# box.net
KiCad netlist of a schematic drawn in EAGLE
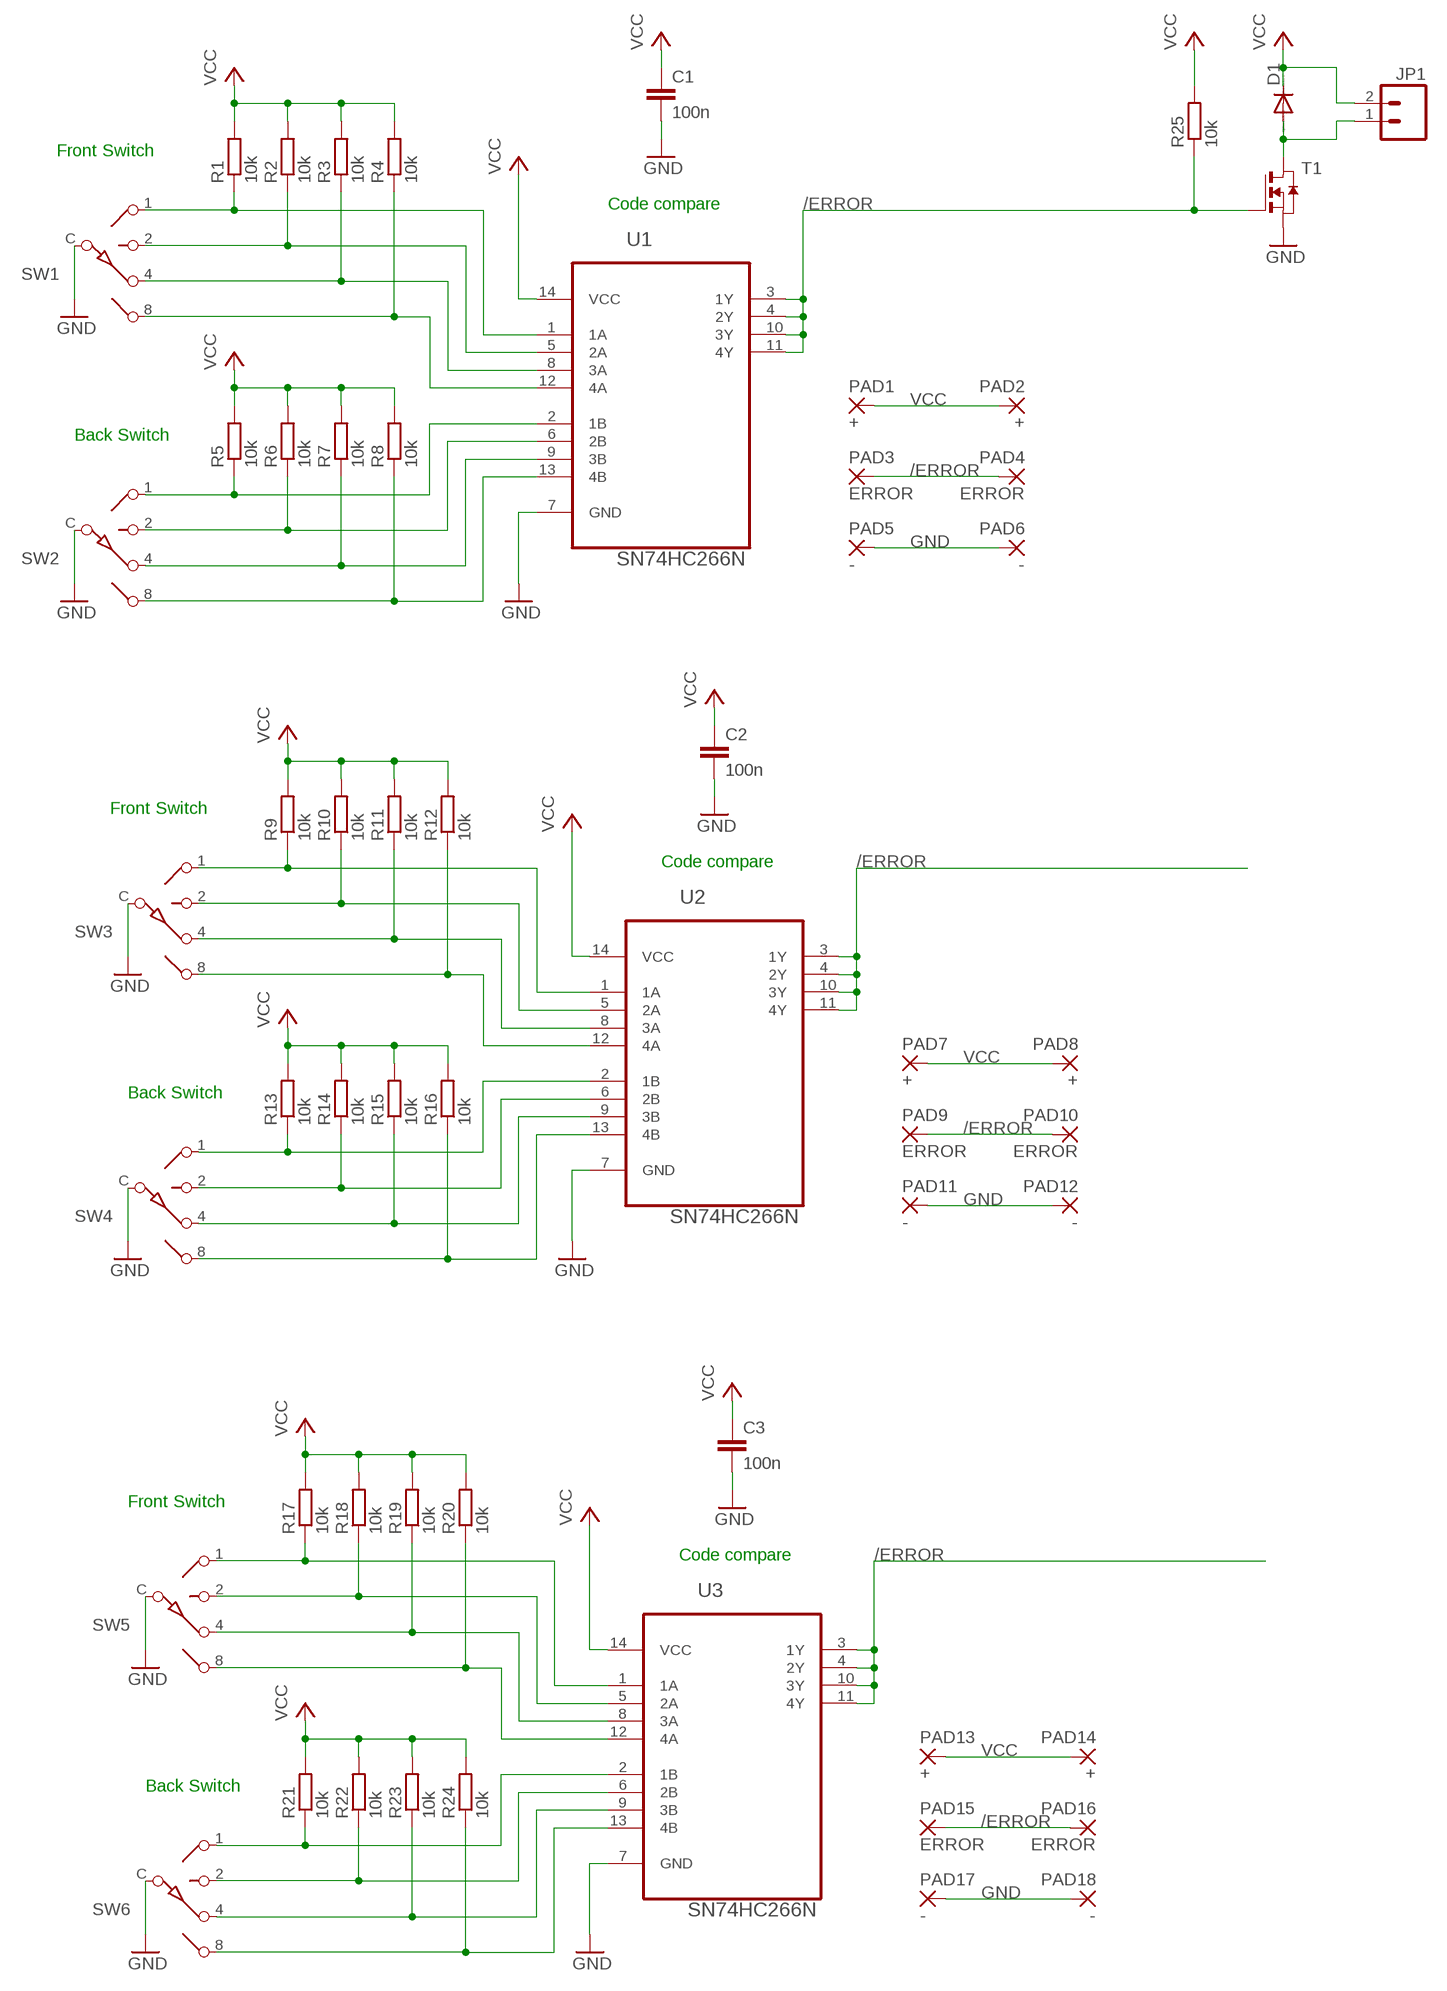
[diagram p0: schematic, sheet 1]

(export (version "E")
  (design (tool "Eeschema 10.0.6"))
  (components
    (comp (ref "C1")
      (value "100n")
      (footprint "eagle-import:C0805")
      (libsource (lib "eagle-import") (part "C-EUC0805"))
    )
    (comp (ref "C2")
      (value "100n")
      (footprint "eagle-import:C0805")
      (libsource (lib "eagle-import") (part "C-EUC0805"))
    )
    (comp (ref "C3")
      (value "100n")
      (footprint "eagle-import:C0805")
      (libsource (lib "eagle-import") (part "C-EUC0805"))
    )
    (comp (ref "D1")
      (value "DIODE-DO41-7.6")
      (footprint "eagle-import:DO41-7.6")
      (libsource (lib "eagle-import") (part "DIODE-DO41-7.6"))
    )
    (comp (ref "JP1")
      (value "M02JST-PTH-2")
      (footprint "eagle-import:JST-2-PTH")
      (libsource (lib "eagle-import") (part "M02JST-PTH-2"))
    )
    (comp (ref "PAD1")
      (value "+")
      (footprint "eagle-import:2,15_1,0")
      (libsource (lib "eagle-import") (part "2,15/1,0"))
    )
    (comp (ref "PAD2")
      (value "+")
      (footprint "eagle-import:2,15_1,0")
      (libsource (lib "eagle-import") (part "2,15/1,0"))
    )
    (comp (ref "PAD3")
      (value "ERROR")
      (footprint "eagle-import:2,15_1,0")
      (libsource (lib "eagle-import") (part "2,15/1,0"))
    )
    (comp (ref "PAD4")
      (value "ERROR")
      (footprint "eagle-import:2,15_1,0")
      (libsource (lib "eagle-import") (part "2,15/1,0"))
    )
    (comp (ref "PAD5")
      (value "-")
      (footprint "eagle-import:2,15_1,0")
      (libsource (lib "eagle-import") (part "2,15/1,0"))
    )
    (comp (ref "PAD6")
      (value "-")
      (footprint "eagle-import:2,15_1,0")
      (libsource (lib "eagle-import") (part "2,15/1,0"))
    )
    (comp (ref "PAD7")
      (value "+")
      (footprint "eagle-import:2,15_1,0")
      (libsource (lib "eagle-import") (part "2,15/1,0"))
    )
    (comp (ref "PAD8")
      (value "+")
      (footprint "eagle-import:2,15_1,0")
      (libsource (lib "eagle-import") (part "2,15/1,0"))
    )
    (comp (ref "PAD9")
      (value "ERROR")
      (footprint "eagle-import:2,15_1,0")
      (libsource (lib "eagle-import") (part "2,15/1,0"))
    )
    (comp (ref "PAD10")
      (value "ERROR")
      (footprint "eagle-import:2,15_1,0")
      (libsource (lib "eagle-import") (part "2,15/1,0"))
    )
    (comp (ref "PAD11")
      (value "-")
      (footprint "eagle-import:2,15_1,0")
      (libsource (lib "eagle-import") (part "2,15/1,0"))
    )
    (comp (ref "PAD12")
      (value "-")
      (footprint "eagle-import:2,15_1,0")
      (libsource (lib "eagle-import") (part "2,15/1,0"))
    )
    (comp (ref "PAD13")
      (value "+")
      (footprint "eagle-import:2,15_1,0")
      (libsource (lib "eagle-import") (part "2,15/1,0"))
    )
    (comp (ref "PAD14")
      (value "+")
      (footprint "eagle-import:2,15_1,0")
      (libsource (lib "eagle-import") (part "2,15/1,0"))
    )
    (comp (ref "PAD15")
      (value "ERROR")
      (footprint "eagle-import:2,15_1,0")
      (libsource (lib "eagle-import") (part "2,15/1,0"))
    )
    (comp (ref "PAD16")
      (value "ERROR")
      (footprint "eagle-import:2,15_1,0")
      (libsource (lib "eagle-import") (part "2,15/1,0"))
    )
    (comp (ref "PAD17")
      (value "-")
      (footprint "eagle-import:2,15_1,0")
      (libsource (lib "eagle-import") (part "2,15/1,0"))
    )
    (comp (ref "PAD18")
      (value "-")
      (footprint "eagle-import:2,15_1,0")
      (libsource (lib "eagle-import") (part "2,15/1,0"))
    )
    (comp (ref "R1")
      (value "10k")
      (footprint "eagle-import:R0805")
      (libsource (lib "eagle-import") (part "R-EU_R0805"))
    )
    (comp (ref "R2")
      (value "10k")
      (footprint "eagle-import:R0805")
      (libsource (lib "eagle-import") (part "R-EU_R0805"))
    )
    (comp (ref "R3")
      (value "10k")
      (footprint "eagle-import:R0805")
      (libsource (lib "eagle-import") (part "R-EU_R0805"))
    )
    (comp (ref "R4")
      (value "10k")
      (footprint "eagle-import:R0805")
      (libsource (lib "eagle-import") (part "R-EU_R0805"))
    )
    (comp (ref "R5")
      (value "10k")
      (footprint "eagle-import:R0805")
      (libsource (lib "eagle-import") (part "R-EU_R0805"))
    )
    (comp (ref "R6")
      (value "10k")
      (footprint "eagle-import:R0805")
      (libsource (lib "eagle-import") (part "R-EU_R0805"))
    )
    (comp (ref "R7")
      (value "10k")
      (footprint "eagle-import:R0805")
      (libsource (lib "eagle-import") (part "R-EU_R0805"))
    )
    (comp (ref "R8")
      (value "10k")
      (footprint "eagle-import:R0805")
      (libsource (lib "eagle-import") (part "R-EU_R0805"))
    )
    (comp (ref "R9")
      (value "10k")
      (footprint "eagle-import:R0805")
      (libsource (lib "eagle-import") (part "R-EU_R0805"))
    )
    (comp (ref "R10")
      (value "10k")
      (footprint "eagle-import:R0805")
      (libsource (lib "eagle-import") (part "R-EU_R0805"))
    )
    (comp (ref "R11")
      (value "10k")
      (footprint "eagle-import:R0805")
      (libsource (lib "eagle-import") (part "R-EU_R0805"))
    )
    (comp (ref "R12")
      (value "10k")
      (footprint "eagle-import:R0805")
      (libsource (lib "eagle-import") (part "R-EU_R0805"))
    )
    (comp (ref "R13")
      (value "10k")
      (footprint "eagle-import:R0805")
      (libsource (lib "eagle-import") (part "R-EU_R0805"))
    )
    (comp (ref "R14")
      (value "10k")
      (footprint "eagle-import:R0805")
      (libsource (lib "eagle-import") (part "R-EU_R0805"))
    )
    (comp (ref "R15")
      (value "10k")
      (footprint "eagle-import:R0805")
      (libsource (lib "eagle-import") (part "R-EU_R0805"))
    )
    (comp (ref "R16")
      (value "10k")
      (footprint "eagle-import:R0805")
      (libsource (lib "eagle-import") (part "R-EU_R0805"))
    )
    (comp (ref "R17")
      (value "10k")
      (footprint "eagle-import:R0805")
      (libsource (lib "eagle-import") (part "R-EU_R0805"))
    )
    (comp (ref "R18")
      (value "10k")
      (footprint "eagle-import:R0805")
      (libsource (lib "eagle-import") (part "R-EU_R0805"))
    )
    (comp (ref "R19")
      (value "10k")
      (footprint "eagle-import:R0805")
      (libsource (lib "eagle-import") (part "R-EU_R0805"))
    )
    (comp (ref "R20")
      (value "10k")
      (footprint "eagle-import:R0805")
      (libsource (lib "eagle-import") (part "R-EU_R0805"))
    )
    (comp (ref "R21")
      (value "10k")
      (footprint "eagle-import:R0805")
      (libsource (lib "eagle-import") (part "R-EU_R0805"))
    )
    (comp (ref "R22")
      (value "10k")
      (footprint "eagle-import:R0805")
      (libsource (lib "eagle-import") (part "R-EU_R0805"))
    )
    (comp (ref "R23")
      (value "10k")
      (footprint "eagle-import:R0805")
      (libsource (lib "eagle-import") (part "R-EU_R0805"))
    )
    (comp (ref "R24")
      (value "10k")
      (footprint "eagle-import:R0805")
      (libsource (lib "eagle-import") (part "R-EU_R0805"))
    )
    (comp (ref "R25")
      (value "10k")
      (footprint "eagle-import:R0805")
      (libsource (lib "eagle-import") (part "R-EU_R0805"))
    )
    (comp (ref "SW1")
      (value "ROTARY-SWITCH-10POSMCRM4HAF-10R-V-B")
      (footprint "eagle-import:MCRM4HAF")
      (libsource (lib "eagle-import") (part "ROTARY-SWITCH-10POSMCRM4HAF-10R-V-B"))
    )
    (comp (ref "SW2")
      (value "ROTARY-SWITCH-10POSMCRM4HAF-10R-V-B")
      (footprint "eagle-import:MCRM4HAF")
      (libsource (lib "eagle-import") (part "ROTARY-SWITCH-10POSMCRM4HAF-10R-V-B"))
    )
    (comp (ref "SW3")
      (value "ROTARY-SWITCH-10POSMCRM4HAF-10R-V-B")
      (footprint "eagle-import:MCRM4HAF")
      (libsource (lib "eagle-import") (part "ROTARY-SWITCH-10POSMCRM4HAF-10R-V-B"))
    )
    (comp (ref "SW4")
      (value "ROTARY-SWITCH-10POSMCRM4HAF-10R-V-B")
      (footprint "eagle-import:MCRM4HAF")
      (libsource (lib "eagle-import") (part "ROTARY-SWITCH-10POSMCRM4HAF-10R-V-B"))
    )
    (comp (ref "SW5")
      (value "ROTARY-SWITCH-10POSMCRM4HAF-10R-V-B")
      (footprint "eagle-import:MCRM4HAF")
      (libsource (lib "eagle-import") (part "ROTARY-SWITCH-10POSMCRM4HAF-10R-V-B"))
    )
    (comp (ref "SW6")
      (value "ROTARY-SWITCH-10POSMCRM4HAF-10R-V-B")
      (footprint "eagle-import:MCRM4HAF")
      (libsource (lib "eagle-import") (part "ROTARY-SWITCH-10POSMCRM4HAF-10R-V-B"))
    )
    (comp (ref "T1")
      (value "TSM3442")
      (footprint "eagle-import:SOT23-6")
      (libsource (lib "eagle-import") (part "TSM3442"))
    )
    (comp (ref "U1")
      (value "SN74HC266N")
      (footprint "eagle-import:DIP254P762X508-14")
      (libsource (lib "eagle-import") (part "SN74HC266N"))
    )
    (comp (ref "U2")
      (value "SN74HC266N")
      (footprint "eagle-import:DIP254P762X508-14")
      (libsource (lib "eagle-import") (part "SN74HC266N"))
    )
    (comp (ref "U3")
      (value "SN74HC266N")
      (footprint "eagle-import:DIP254P762X508-14")
      (libsource (lib "eagle-import") (part "SN74HC266N"))
    )
  )
  (nets
    (net (code "1") (name "/{slash}ERROR") (class "Default")
      (node (ref "PAD10") (pin "1") (pinfunction "P_1") (pintype "passive"))
      (node (ref "PAD15") (pin "1") (pinfunction "P_1") (pintype "passive"))
      (node (ref "PAD16") (pin "1") (pinfunction "P_1") (pintype "passive"))
      (node (ref "PAD3") (pin "1") (pinfunction "P_1") (pintype "passive"))
      (node (ref "PAD4") (pin "1") (pinfunction "P_1") (pintype "passive"))
      (node (ref "PAD9") (pin "1") (pinfunction "P_1") (pintype "passive"))
      (node (ref "R25") (pin "1") (pinfunction "1_1") (pintype "passive"))
      (node (ref "T1") (pin "3") (pinfunction "G_3") (pintype "passive"))
      (node (ref "U1") (pin "10") (pinfunction "3Y_10") (pintype "output"))
      (node (ref "U1") (pin "11") (pinfunction "4Y_11") (pintype "output"))
      (node (ref "U1") (pin "3") (pinfunction "1Y_3") (pintype "output"))
      (node (ref "U1") (pin "4") (pinfunction "2Y_4") (pintype "output"))
      (node (ref "U2") (pin "10") (pinfunction "3Y_10") (pintype "output"))
      (node (ref "U2") (pin "11") (pinfunction "4Y_11") (pintype "output"))
      (node (ref "U2") (pin "3") (pinfunction "1Y_3") (pintype "output"))
      (node (ref "U2") (pin "4") (pinfunction "2Y_4") (pintype "output"))
      (node (ref "U3") (pin "10") (pinfunction "3Y_10") (pintype "output"))
      (node (ref "U3") (pin "11") (pinfunction "4Y_11") (pintype "output"))
      (node (ref "U3") (pin "3") (pinfunction "1Y_3") (pintype "output"))
      (node (ref "U3") (pin "4") (pinfunction "2Y_4") (pintype "output"))
    )
    (net (code "2") (name "GND") (class "Default")
      (node (ref "C1") (pin "2") (pinfunction "2_2") (pintype "passive"))
      (node (ref "C2") (pin "2") (pinfunction "2_2") (pintype "passive"))
      (node (ref "C3") (pin "2") (pinfunction "2_2") (pintype "passive"))
      (node (ref "PAD11") (pin "1") (pinfunction "P_1") (pintype "passive"))
      (node (ref "PAD12") (pin "1") (pinfunction "P_1") (pintype "passive"))
      (node (ref "PAD17") (pin "1") (pinfunction "P_1") (pintype "passive"))
      (node (ref "PAD18") (pin "1") (pinfunction "P_1") (pintype "passive"))
      (node (ref "PAD5") (pin "1") (pinfunction "P_1") (pintype "passive"))
      (node (ref "PAD6") (pin "1") (pinfunction "P_1") (pintype "passive"))
      (node (ref "SW1") (pin "C") (pinfunction "C_C") (pintype "passive"))
      (node (ref "SW2") (pin "C") (pinfunction "C_C") (pintype "passive"))
      (node (ref "SW3") (pin "C") (pinfunction "C_C") (pintype "passive"))
      (node (ref "SW4") (pin "C") (pinfunction "C_C") (pintype "passive"))
      (node (ref "SW5") (pin "C") (pinfunction "C_C") (pintype "passive"))
      (node (ref "SW6") (pin "C") (pinfunction "C_C") (pintype "passive"))
      (node (ref "T1") (pin "4") (pinfunction "S_4") (pintype "passive"))
      (node (ref "U1") (pin "7") (pinfunction "GND_7") (pintype "passive"))
      (node (ref "U2") (pin "7") (pinfunction "GND_7") (pintype "passive"))
      (node (ref "U3") (pin "7") (pinfunction "GND_7") (pintype "passive"))
    )
    (net (code "3") (name "Net-(D1-PadA)") (class "Default")
      (node (ref "D1") (pin "A") (pinfunction "A_A") (pintype "passive"))
      (node (ref "JP1") (pin "1") (pinfunction "1_1") (pintype "passive"))
      (node (ref "T1") (pin "1") (pinfunction "D_1") (pintype "passive"))
      (node (ref "T1") (pin "2") (pinfunction "D_2") (pintype "passive"))
      (node (ref "T1") (pin "5") (pinfunction "D_5") (pintype "passive"))
      (node (ref "T1") (pin "6") (pinfunction "D_6") (pintype "passive"))
    )
    (net (code "4") (name "Net-(U1-1A)") (class "Default")
      (node (ref "R1") (pin "1") (pinfunction "1_1") (pintype "passive"))
      (node (ref "SW1") (pin "1") (pinfunction "1_1") (pintype "passive"))
      (node (ref "U1") (pin "1") (pinfunction "1A_1") (pintype "input"))
    )
    (net (code "5") (name "Net-(U1-1B)") (class "Default")
      (node (ref "R5") (pin "1") (pinfunction "1_1") (pintype "passive"))
      (node (ref "SW2") (pin "1") (pinfunction "1_1") (pintype "passive"))
      (node (ref "U1") (pin "2") (pinfunction "1B_2") (pintype "input"))
    )
    (net (code "6") (name "Net-(U1-2A)") (class "Default")
      (node (ref "R2") (pin "1") (pinfunction "1_1") (pintype "passive"))
      (node (ref "SW1") (pin "2") (pinfunction "2_2") (pintype "passive"))
      (node (ref "U1") (pin "5") (pinfunction "2A_5") (pintype "input"))
    )
    (net (code "7") (name "Net-(U1-2B)") (class "Default")
      (node (ref "R6") (pin "1") (pinfunction "1_1") (pintype "passive"))
      (node (ref "SW2") (pin "2") (pinfunction "2_2") (pintype "passive"))
      (node (ref "U1") (pin "6") (pinfunction "2B_6") (pintype "input"))
    )
    (net (code "8") (name "Net-(U1-3A)") (class "Default")
      (node (ref "R3") (pin "1") (pinfunction "1_1") (pintype "passive"))
      (node (ref "SW1") (pin "4") (pinfunction "4_4") (pintype "passive"))
      (node (ref "U1") (pin "8") (pinfunction "3A_8") (pintype "input"))
    )
    (net (code "9") (name "Net-(U1-3B)") (class "Default")
      (node (ref "R7") (pin "1") (pinfunction "1_1") (pintype "passive"))
      (node (ref "SW2") (pin "4") (pinfunction "4_4") (pintype "passive"))
      (node (ref "U1") (pin "9") (pinfunction "3B_9") (pintype "input"))
    )
    (net (code "10") (name "Net-(U1-4A)") (class "Default")
      (node (ref "R4") (pin "1") (pinfunction "1_1") (pintype "passive"))
      (node (ref "SW1") (pin "8") (pinfunction "8_8") (pintype "passive"))
      (node (ref "U1") (pin "12") (pinfunction "4A_12") (pintype "input"))
    )
    (net (code "11") (name "Net-(U1-4B)") (class "Default")
      (node (ref "R8") (pin "1") (pinfunction "1_1") (pintype "passive"))
      (node (ref "SW2") (pin "8") (pinfunction "8_8") (pintype "passive"))
      (node (ref "U1") (pin "13") (pinfunction "4B_13") (pintype "input"))
    )
    (net (code "12") (name "Net-(U2-1A)") (class "Default")
      (node (ref "R9") (pin "1") (pinfunction "1_1") (pintype "passive"))
      (node (ref "SW3") (pin "1") (pinfunction "1_1") (pintype "passive"))
      (node (ref "U2") (pin "1") (pinfunction "1A_1") (pintype "input"))
    )
    (net (code "13") (name "Net-(U2-1B)") (class "Default")
      (node (ref "R13") (pin "1") (pinfunction "1_1") (pintype "passive"))
      (node (ref "SW4") (pin "1") (pinfunction "1_1") (pintype "passive"))
      (node (ref "U2") (pin "2") (pinfunction "1B_2") (pintype "input"))
    )
    (net (code "14") (name "Net-(U2-2A)") (class "Default")
      (node (ref "R10") (pin "1") (pinfunction "1_1") (pintype "passive"))
      (node (ref "SW3") (pin "2") (pinfunction "2_2") (pintype "passive"))
      (node (ref "U2") (pin "5") (pinfunction "2A_5") (pintype "input"))
    )
    (net (code "15") (name "Net-(U2-2B)") (class "Default")
      (node (ref "R14") (pin "1") (pinfunction "1_1") (pintype "passive"))
      (node (ref "SW4") (pin "2") (pinfunction "2_2") (pintype "passive"))
      (node (ref "U2") (pin "6") (pinfunction "2B_6") (pintype "input"))
    )
    (net (code "16") (name "Net-(U2-3A)") (class "Default")
      (node (ref "R11") (pin "1") (pinfunction "1_1") (pintype "passive"))
      (node (ref "SW3") (pin "4") (pinfunction "4_4") (pintype "passive"))
      (node (ref "U2") (pin "8") (pinfunction "3A_8") (pintype "input"))
    )
    (net (code "17") (name "Net-(U2-3B)") (class "Default")
      (node (ref "R15") (pin "1") (pinfunction "1_1") (pintype "passive"))
      (node (ref "SW4") (pin "4") (pinfunction "4_4") (pintype "passive"))
      (node (ref "U2") (pin "9") (pinfunction "3B_9") (pintype "input"))
    )
    (net (code "18") (name "Net-(U2-4A)") (class "Default")
      (node (ref "R12") (pin "1") (pinfunction "1_1") (pintype "passive"))
      (node (ref "SW3") (pin "8") (pinfunction "8_8") (pintype "passive"))
      (node (ref "U2") (pin "12") (pinfunction "4A_12") (pintype "input"))
    )
    (net (code "19") (name "Net-(U2-4B)") (class "Default")
      (node (ref "R16") (pin "1") (pinfunction "1_1") (pintype "passive"))
      (node (ref "SW4") (pin "8") (pinfunction "8_8") (pintype "passive"))
      (node (ref "U2") (pin "13") (pinfunction "4B_13") (pintype "input"))
    )
    (net (code "20") (name "Net-(U3-1A)") (class "Default")
      (node (ref "R17") (pin "1") (pinfunction "1_1") (pintype "passive"))
      (node (ref "SW5") (pin "1") (pinfunction "1_1") (pintype "passive"))
      (node (ref "U3") (pin "1") (pinfunction "1A_1") (pintype "input"))
    )
    (net (code "21") (name "Net-(U3-1B)") (class "Default")
      (node (ref "R21") (pin "1") (pinfunction "1_1") (pintype "passive"))
      (node (ref "SW6") (pin "1") (pinfunction "1_1") (pintype "passive"))
      (node (ref "U3") (pin "2") (pinfunction "1B_2") (pintype "input"))
    )
    (net (code "22") (name "Net-(U3-2A)") (class "Default")
      (node (ref "R18") (pin "1") (pinfunction "1_1") (pintype "passive"))
      (node (ref "SW5") (pin "2") (pinfunction "2_2") (pintype "passive"))
      (node (ref "U3") (pin "5") (pinfunction "2A_5") (pintype "input"))
    )
    (net (code "23") (name "Net-(U3-2B)") (class "Default")
      (node (ref "R22") (pin "1") (pinfunction "1_1") (pintype "passive"))
      (node (ref "SW6") (pin "2") (pinfunction "2_2") (pintype "passive"))
      (node (ref "U3") (pin "6") (pinfunction "2B_6") (pintype "input"))
    )
    (net (code "24") (name "Net-(U3-3A)") (class "Default")
      (node (ref "R19") (pin "1") (pinfunction "1_1") (pintype "passive"))
      (node (ref "SW5") (pin "4") (pinfunction "4_4") (pintype "passive"))
      (node (ref "U3") (pin "8") (pinfunction "3A_8") (pintype "input"))
    )
    (net (code "25") (name "Net-(U3-3B)") (class "Default")
      (node (ref "R23") (pin "1") (pinfunction "1_1") (pintype "passive"))
      (node (ref "SW6") (pin "4") (pinfunction "4_4") (pintype "passive"))
      (node (ref "U3") (pin "9") (pinfunction "3B_9") (pintype "input"))
    )
    (net (code "26") (name "Net-(U3-4A)") (class "Default")
      (node (ref "R20") (pin "1") (pinfunction "1_1") (pintype "passive"))
      (node (ref "SW5") (pin "8") (pinfunction "8_8") (pintype "passive"))
      (node (ref "U3") (pin "12") (pinfunction "4A_12") (pintype "input"))
    )
    (net (code "27") (name "Net-(U3-4B)") (class "Default")
      (node (ref "R24") (pin "1") (pinfunction "1_1") (pintype "passive"))
      (node (ref "SW6") (pin "8") (pinfunction "8_8") (pintype "passive"))
      (node (ref "U3") (pin "13") (pinfunction "4B_13") (pintype "input"))
    )
    (net (code "28") (name "VCC") (class "Default")
      (node (ref "C1") (pin "1") (pinfunction "1_1") (pintype "passive"))
      (node (ref "C2") (pin "1") (pinfunction "1_1") (pintype "passive"))
      (node (ref "C3") (pin "1") (pinfunction "1_1") (pintype "passive"))
      (node (ref "D1") (pin "C") (pinfunction "C_C") (pintype "passive"))
      (node (ref "JP1") (pin "2") (pinfunction "2_2") (pintype "passive"))
      (node (ref "PAD1") (pin "1") (pinfunction "P_1") (pintype "passive"))
      (node (ref "PAD13") (pin "1") (pinfunction "P_1") (pintype "passive"))
      (node (ref "PAD14") (pin "1") (pinfunction "P_1") (pintype "passive"))
      (node (ref "PAD2") (pin "1") (pinfunction "P_1") (pintype "passive"))
      (node (ref "PAD7") (pin "1") (pinfunction "P_1") (pintype "passive"))
      (node (ref "PAD8") (pin "1") (pinfunction "P_1") (pintype "passive"))
      (node (ref "R1") (pin "2") (pinfunction "2_2") (pintype "passive"))
      (node (ref "R10") (pin "2") (pinfunction "2_2") (pintype "passive"))
      (node (ref "R11") (pin "2") (pinfunction "2_2") (pintype "passive"))
      (node (ref "R12") (pin "2") (pinfunction "2_2") (pintype "passive"))
      (node (ref "R13") (pin "2") (pinfunction "2_2") (pintype "passive"))
      (node (ref "R14") (pin "2") (pinfunction "2_2") (pintype "passive"))
      (node (ref "R15") (pin "2") (pinfunction "2_2") (pintype "passive"))
      (node (ref "R16") (pin "2") (pinfunction "2_2") (pintype "passive"))
      (node (ref "R17") (pin "2") (pinfunction "2_2") (pintype "passive"))
      (node (ref "R18") (pin "2") (pinfunction "2_2") (pintype "passive"))
      (node (ref "R19") (pin "2") (pinfunction "2_2") (pintype "passive"))
      (node (ref "R2") (pin "2") (pinfunction "2_2") (pintype "passive"))
      (node (ref "R20") (pin "2") (pinfunction "2_2") (pintype "passive"))
      (node (ref "R21") (pin "2") (pinfunction "2_2") (pintype "passive"))
      (node (ref "R22") (pin "2") (pinfunction "2_2") (pintype "passive"))
      (node (ref "R23") (pin "2") (pinfunction "2_2") (pintype "passive"))
      (node (ref "R24") (pin "2") (pinfunction "2_2") (pintype "passive"))
      (node (ref "R25") (pin "2") (pinfunction "2_2") (pintype "passive"))
      (node (ref "R3") (pin "2") (pinfunction "2_2") (pintype "passive"))
      (node (ref "R4") (pin "2") (pinfunction "2_2") (pintype "passive"))
      (node (ref "R5") (pin "2") (pinfunction "2_2") (pintype "passive"))
      (node (ref "R6") (pin "2") (pinfunction "2_2") (pintype "passive"))
      (node (ref "R7") (pin "2") (pinfunction "2_2") (pintype "passive"))
      (node (ref "R8") (pin "2") (pinfunction "2_2") (pintype "passive"))
      (node (ref "R9") (pin "2") (pinfunction "2_2") (pintype "passive"))
      (node (ref "U1") (pin "14") (pinfunction "VCC_14") (pintype "power_in"))
      (node (ref "U2") (pin "14") (pinfunction "VCC_14") (pintype "power_in"))
      (node (ref "U3") (pin "14") (pinfunction "VCC_14") (pintype "power_in"))
    )
  )
)
